# CAN-IO.net
KiCad netlist of a schematic drawn in EAGLE
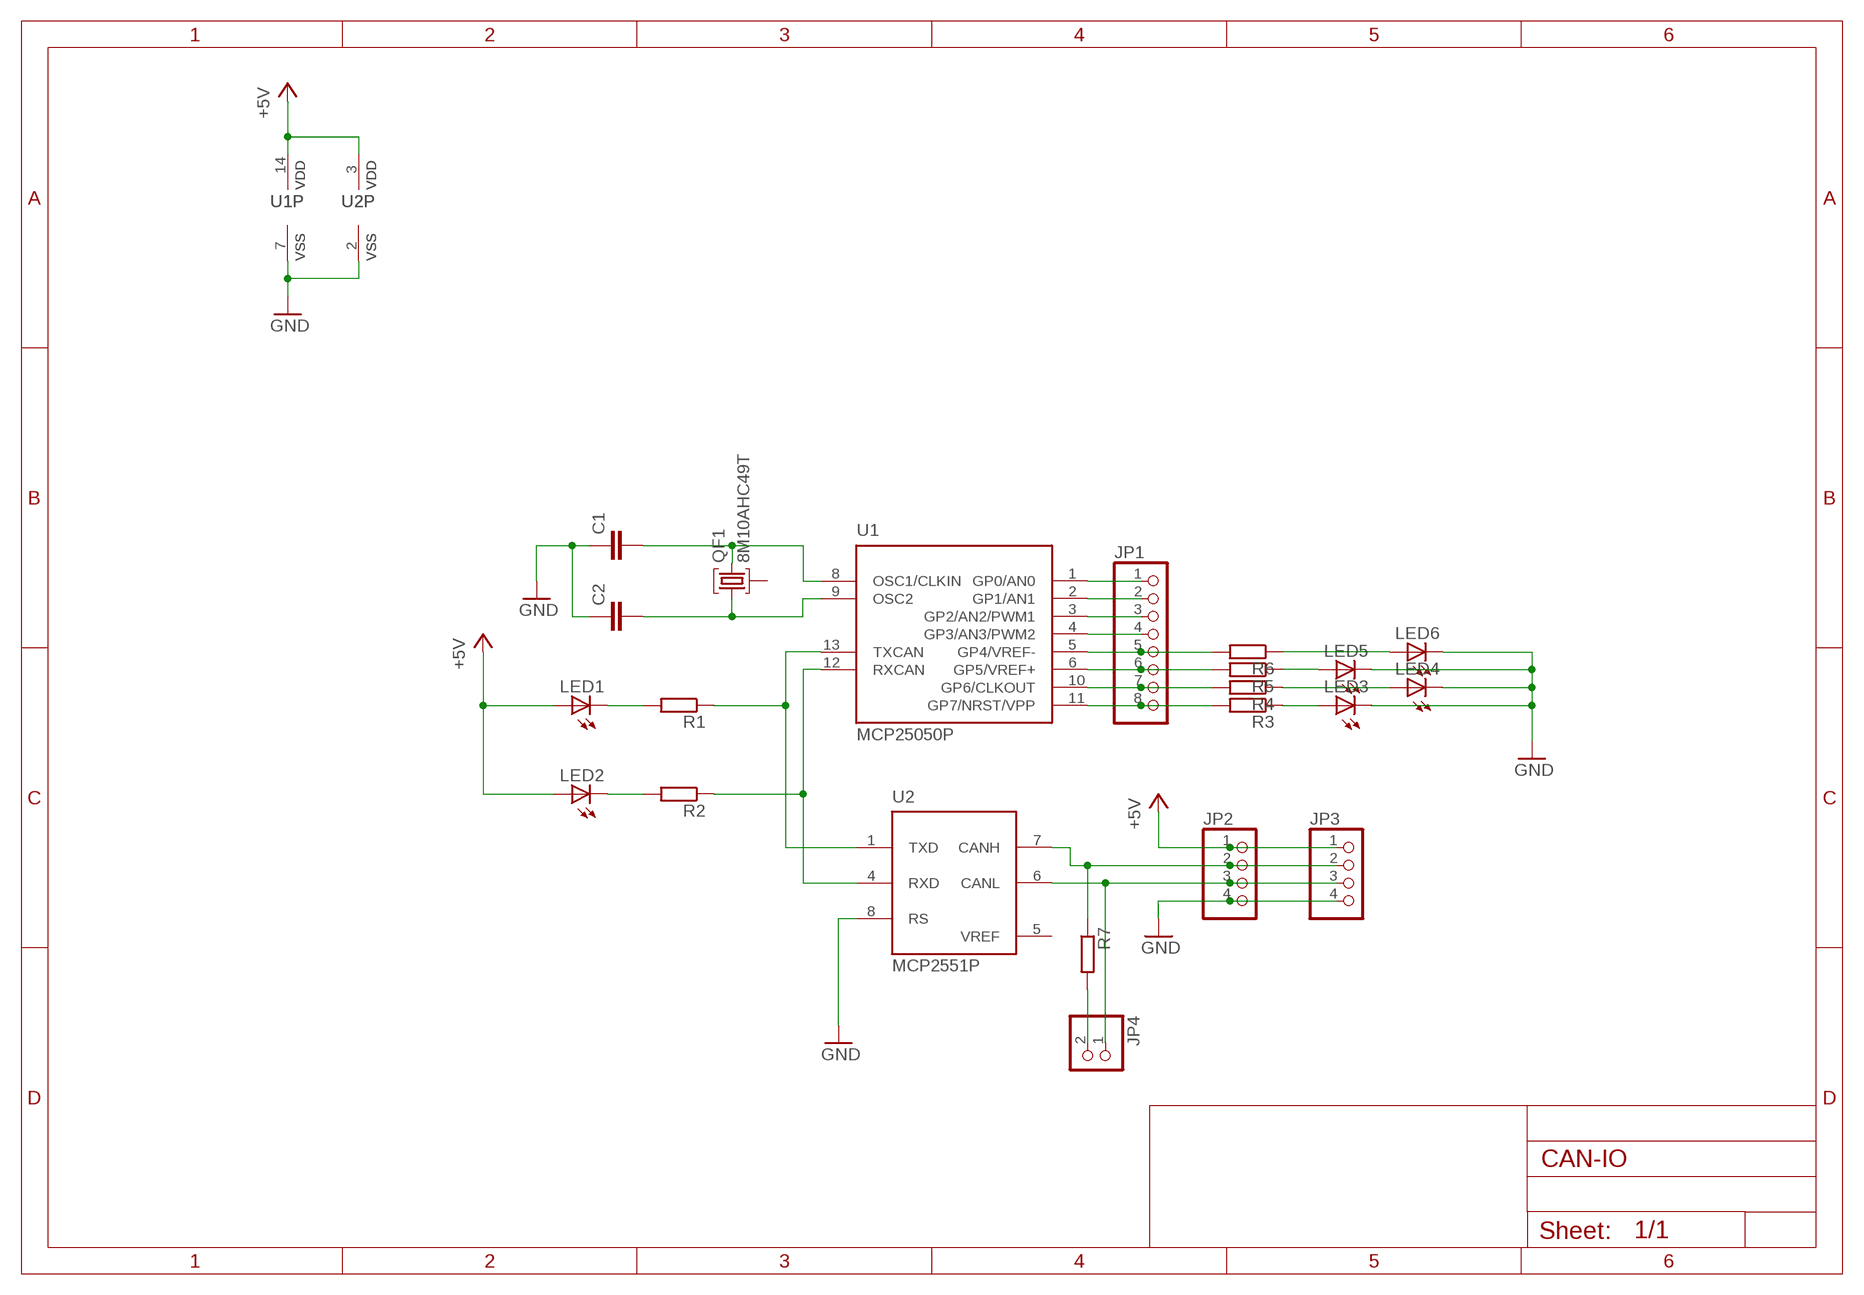
[diagram p0: schematic, sheet 1]

(export (version "E")
  (design (tool "Eeschema 10.0.6"))
  (components
    (comp (ref "C1")
      (value "C-EU025-024X044")
      (footprint "eagle-import:C025-024X044")
      (libsource (lib "eagle-import") (part "C-EU025-024X044"))
    )
    (comp (ref "C2")
      (value "C-EU025-024X044")
      (footprint "eagle-import:C025-024X044")
      (libsource (lib "eagle-import") (part "C-EU025-024X044"))
    )
    (comp (ref "JP1")
      (value "PINHD-1X8")
      (footprint "eagle-import:1X08")
      (libsource (lib "eagle-import") (part "PINHD-1X8"))
    )
    (comp (ref "JP2")
      (value "PINHD-1X4/90")
      (footprint "eagle-import:1X04_90")
      (libsource (lib "eagle-import") (part "PINHD-1X4/90"))
    )
    (comp (ref "JP3")
      (value "PINHD-1X4/90")
      (footprint "eagle-import:1X04_90")
      (libsource (lib "eagle-import") (part "PINHD-1X4/90"))
    )
    (comp (ref "JP4")
      (value "PINHD-1X2")
      (footprint "eagle-import:1X02")
      (libsource (lib "eagle-import") (part "PINHD-1X2"))
    )
    (comp (ref "LED1")
      (value "LED5MM")
      (footprint "eagle-import:LED5MM")
      (libsource (lib "eagle-import") (part "LED5MM"))
    )
    (comp (ref "LED2")
      (value "LED5MM")
      (footprint "eagle-import:LED5MM")
      (libsource (lib "eagle-import") (part "LED5MM"))
    )
    (comp (ref "LED3")
      (value "LED5MM")
      (footprint "eagle-import:LED5MM")
      (libsource (lib "eagle-import") (part "LED5MM"))
    )
    (comp (ref "LED4")
      (value "LED5MM")
      (footprint "eagle-import:LED5MM")
      (libsource (lib "eagle-import") (part "LED5MM"))
    )
    (comp (ref "LED5")
      (value "LED5MM")
      (footprint "eagle-import:LED5MM")
      (libsource (lib "eagle-import") (part "LED5MM"))
    )
    (comp (ref "LED6")
      (value "LED5MM")
      (footprint "eagle-import:LED5MM")
      (libsource (lib "eagle-import") (part "LED5MM"))
    )
    (comp (ref "QF1")
      (value "8M10AHC49T")
      (footprint "eagle-import:HC49U")
      (libsource (lib "eagle-import") (part "8M10AHC49T"))
    )
    (comp (ref "R1")
      (value "R-EU_0207/10")
      (footprint "eagle-import:0207_10")
      (libsource (lib "eagle-import") (part "R-EU_0207/10"))
    )
    (comp (ref "R2")
      (value "R-EU_0207/10")
      (footprint "eagle-import:0207_10")
      (libsource (lib "eagle-import") (part "R-EU_0207/10"))
    )
    (comp (ref "R3")
      (value "R-EU_0207/10")
      (footprint "eagle-import:0207_10")
      (libsource (lib "eagle-import") (part "R-EU_0207/10"))
    )
    (comp (ref "R4")
      (value "R-EU_0207/10")
      (footprint "eagle-import:0207_10")
      (libsource (lib "eagle-import") (part "R-EU_0207/10"))
    )
    (comp (ref "R5")
      (value "R-EU_0207/10")
      (footprint "eagle-import:0207_10")
      (libsource (lib "eagle-import") (part "R-EU_0207/10"))
    )
    (comp (ref "R6")
      (value "R-EU_0207/10")
      (footprint "eagle-import:0207_10")
      (libsource (lib "eagle-import") (part "R-EU_0207/10"))
    )
    (comp (ref "R7")
      (value "R-EU_0207/10")
      (footprint "eagle-import:0207_10")
      (libsource (lib "eagle-import") (part "R-EU_0207/10"))
    )
    (comp (ref "U1")
      (value "MCP25050P")
      (footprint "eagle-import:DIL14")
      (libsource (lib "eagle-import") (part "MCP25050P"))
    )
    (comp (ref "U2")
      (value "MCP2551P")
      (footprint "eagle-import:DIL8")
      (libsource (lib "eagle-import") (part "MCP2551P"))
    )
  )
  (nets
    (net (code "1") (name "+5V") (class "Default")
      (node (ref "JP2") (pin "1") (pinfunction "1_1") (pintype "passive"))
      (node (ref "JP3") (pin "1") (pinfunction "1_1") (pintype "passive"))
      (node (ref "LED1") (pin "A") (pinfunction "A_A") (pintype "passive"))
      (node (ref "LED2") (pin "A") (pinfunction "A_A") (pintype "passive"))
      (node (ref "U1") (pin "14") (pinfunction "VDD_14") (pintype "power_in"))
      (node (ref "U2") (pin "3") (pinfunction "VDD_3") (pintype "power_in"))
    )
    (net (code "2") (name "/VREF") (class "Default")
      (node (ref "U2") (pin "5") (pinfunction "VREF_5") (pintype "power_in"))
    )
    (net (code "3") (name "GND") (class "Default")
      (node (ref "C1") (pin "1") (pinfunction "1_1") (pintype "passive"))
      (node (ref "C2") (pin "1") (pinfunction "1_1") (pintype "passive"))
      (node (ref "JP2") (pin "4") (pinfunction "4_4") (pintype "passive"))
      (node (ref "JP3") (pin "4") (pinfunction "4_4") (pintype "passive"))
      (node (ref "LED3") (pin "K") (pinfunction "C_K") (pintype "passive"))
      (node (ref "LED4") (pin "K") (pinfunction "C_K") (pintype "passive"))
      (node (ref "LED5") (pin "K") (pinfunction "C_K") (pintype "passive"))
      (node (ref "LED6") (pin "K") (pinfunction "C_K") (pintype "passive"))
      (node (ref "U1") (pin "7") (pinfunction "VSS_7") (pintype "power_in"))
      (node (ref "U2") (pin "2") (pinfunction "VSS_2") (pintype "power_in"))
      (node (ref "U2") (pin "8") (pinfunction "RS_8") (pintype "input"))
    )
    (net (code "4") (name "Net-(JP4-Pad2)") (class "Default")
      (node (ref "JP4") (pin "2") (pinfunction "2_2") (pintype "passive"))
      (node (ref "R7") (pin "2") (pinfunction "2_2") (pintype "passive"))
    )
    (net (code "5") (name "Net-(LED1-C)") (class "Default")
      (node (ref "LED1") (pin "K") (pinfunction "C_K") (pintype "passive"))
      (node (ref "R1") (pin "2") (pinfunction "2_2") (pintype "passive"))
    )
    (net (code "6") (name "Net-(LED2-C)") (class "Default")
      (node (ref "LED2") (pin "K") (pinfunction "C_K") (pintype "passive"))
      (node (ref "R2") (pin "2") (pinfunction "2_2") (pintype "passive"))
    )
    (net (code "7") (name "Net-(LED3-PadA)") (class "Default")
      (node (ref "LED3") (pin "A") (pinfunction "A_A") (pintype "passive"))
      (node (ref "R3") (pin "1") (pinfunction "1_1") (pintype "passive"))
    )
    (net (code "8") (name "Net-(LED4-PadA)") (class "Default")
      (node (ref "LED4") (pin "A") (pinfunction "A_A") (pintype "passive"))
      (node (ref "R4") (pin "1") (pinfunction "1_1") (pintype "passive"))
    )
    (net (code "9") (name "Net-(LED5-PadA)") (class "Default")
      (node (ref "LED5") (pin "A") (pinfunction "A_A") (pintype "passive"))
      (node (ref "R5") (pin "1") (pinfunction "1_1") (pintype "passive"))
    )
    (net (code "10") (name "Net-(LED6-PadA)") (class "Default")
      (node (ref "LED6") (pin "A") (pinfunction "A_A") (pintype "passive"))
      (node (ref "R6") (pin "1") (pinfunction "1_1") (pintype "passive"))
    )
    (net (code "11") (name "Net-(U1A-GP0{slash}AN0)") (class "Default")
      (node (ref "JP1") (pin "1") (pinfunction "1_1") (pintype "passive"))
      (node (ref "U1") (pin "1") (pinfunction "GP0/AN0_1") (pintype "bidirectional"))
    )
    (net (code "12") (name "Net-(U1A-GP1{slash}AN1)") (class "Default")
      (node (ref "JP1") (pin "2") (pinfunction "2_2") (pintype "passive"))
      (node (ref "U1") (pin "2") (pinfunction "GP1/AN1_2") (pintype "bidirectional"))
    )
    (net (code "13") (name "Net-(U1A-GP2{slash}AN2{slash}PWM1)") (class "Default")
      (node (ref "JP1") (pin "3") (pinfunction "3_3") (pintype "passive"))
      (node (ref "U1") (pin "3") (pinfunction "GP2/AN2/PWM1_3") (pintype "bidirectional"))
    )
    (net (code "14") (name "Net-(U1A-GP3{slash}AN3{slash}PWM2)") (class "Default")
      (node (ref "JP1") (pin "4") (pinfunction "4_4") (pintype "passive"))
      (node (ref "U1") (pin "4") (pinfunction "GP3/AN3/PWM2_4") (pintype "bidirectional"))
    )
    (net (code "15") (name "Net-(U1A-GP4{slash}VREF-)") (class "Default")
      (node (ref "JP1") (pin "5") (pinfunction "5_5") (pintype "passive"))
      (node (ref "R6") (pin "2") (pinfunction "2_2") (pintype "passive"))
      (node (ref "U1") (pin "5") (pinfunction "GP4/VREF-_5") (pintype "bidirectional"))
    )
    (net (code "16") (name "Net-(U1A-GP5{slash}VREF+)") (class "Default")
      (node (ref "JP1") (pin "6") (pinfunction "6_6") (pintype "passive"))
      (node (ref "R5") (pin "2") (pinfunction "2_2") (pintype "passive"))
      (node (ref "U1") (pin "6") (pinfunction "GP5/VREF+_6") (pintype "bidirectional"))
    )
    (net (code "17") (name "Net-(U1A-GP6{slash}CLKOUT)") (class "Default")
      (node (ref "JP1") (pin "7") (pinfunction "7_7") (pintype "passive"))
      (node (ref "R4") (pin "2") (pinfunction "2_2") (pintype "passive"))
      (node (ref "U1") (pin "10") (pinfunction "GP6/CLKOUT_10") (pintype "bidirectional"))
    )
    (net (code "18") (name "Net-(U1A-GP7{slash}NRST{slash}VPP)") (class "Default")
      (node (ref "JP1") (pin "8") (pinfunction "8_8") (pintype "passive"))
      (node (ref "R3") (pin "2") (pinfunction "2_2") (pintype "passive"))
      (node (ref "U1") (pin "11") (pinfunction "GP7/NRST/VPP_11") (pintype "bidirectional"))
    )
    (net (code "19") (name "Net-(U1A-OSC1{slash}CLKIN)") (class "Default")
      (node (ref "C1") (pin "2") (pinfunction "2_2") (pintype "passive"))
      (node (ref "QF1") (pin "3") (pinfunction "3_3") (pintype "passive"))
      (node (ref "U1") (pin "8") (pinfunction "OSC1/CLKIN_8") (pintype "input"))
    )
    (net (code "20") (name "Net-(U1A-OSC2)") (class "Default")
      (node (ref "C2") (pin "2") (pinfunction "2_2") (pintype "passive"))
      (node (ref "QF1") (pin "1") (pinfunction "1_1") (pintype "passive"))
      (node (ref "U1") (pin "9") (pinfunction "OSC2_9") (pintype "output"))
    )
    (net (code "21") (name "Net-(U1A-RXCAN)") (class "Default")
      (node (ref "R2") (pin "1") (pinfunction "1_1") (pintype "passive"))
      (node (ref "U1") (pin "12") (pinfunction "RXCAN_12") (pintype "input"))
      (node (ref "U2") (pin "4") (pinfunction "RXD_4") (pintype "output"))
    )
    (net (code "22") (name "Net-(U1A-TXCAN)") (class "Default")
      (node (ref "R1") (pin "1") (pinfunction "1_1") (pintype "passive"))
      (node (ref "U1") (pin "13") (pinfunction "TXCAN_13") (pintype "output"))
      (node (ref "U2") (pin "1") (pinfunction "TXD_1") (pintype "input"))
    )
    (net (code "23") (name "Net-(U2A-CANH)") (class "Default")
      (node (ref "JP2") (pin "2") (pinfunction "2_2") (pintype "passive"))
      (node (ref "JP3") (pin "2") (pinfunction "2_2") (pintype "passive"))
      (node (ref "R7") (pin "1") (pinfunction "1_1") (pintype "passive"))
      (node (ref "U2") (pin "7") (pinfunction "CANH_7") (pintype "bidirectional"))
    )
    (net (code "24") (name "Net-(U2A-CANL)") (class "Default")
      (node (ref "JP2") (pin "3") (pinfunction "3_3") (pintype "passive"))
      (node (ref "JP3") (pin "3") (pinfunction "3_3") (pintype "passive"))
      (node (ref "JP4") (pin "1") (pinfunction "1_1") (pintype "passive"))
      (node (ref "U2") (pin "6") (pinfunction "CANL_6") (pintype "bidirectional"))
    )
    (net (code "25") (name "unconnected-(QF1-Pad2)") (class "Default")
      (node (ref "QF1") (pin "2") (pinfunction "2_2") (pintype "passive"))
    )
  )
)
